# painel_meb.net
KiCad netlist of a schematic drawn in Altium Designer
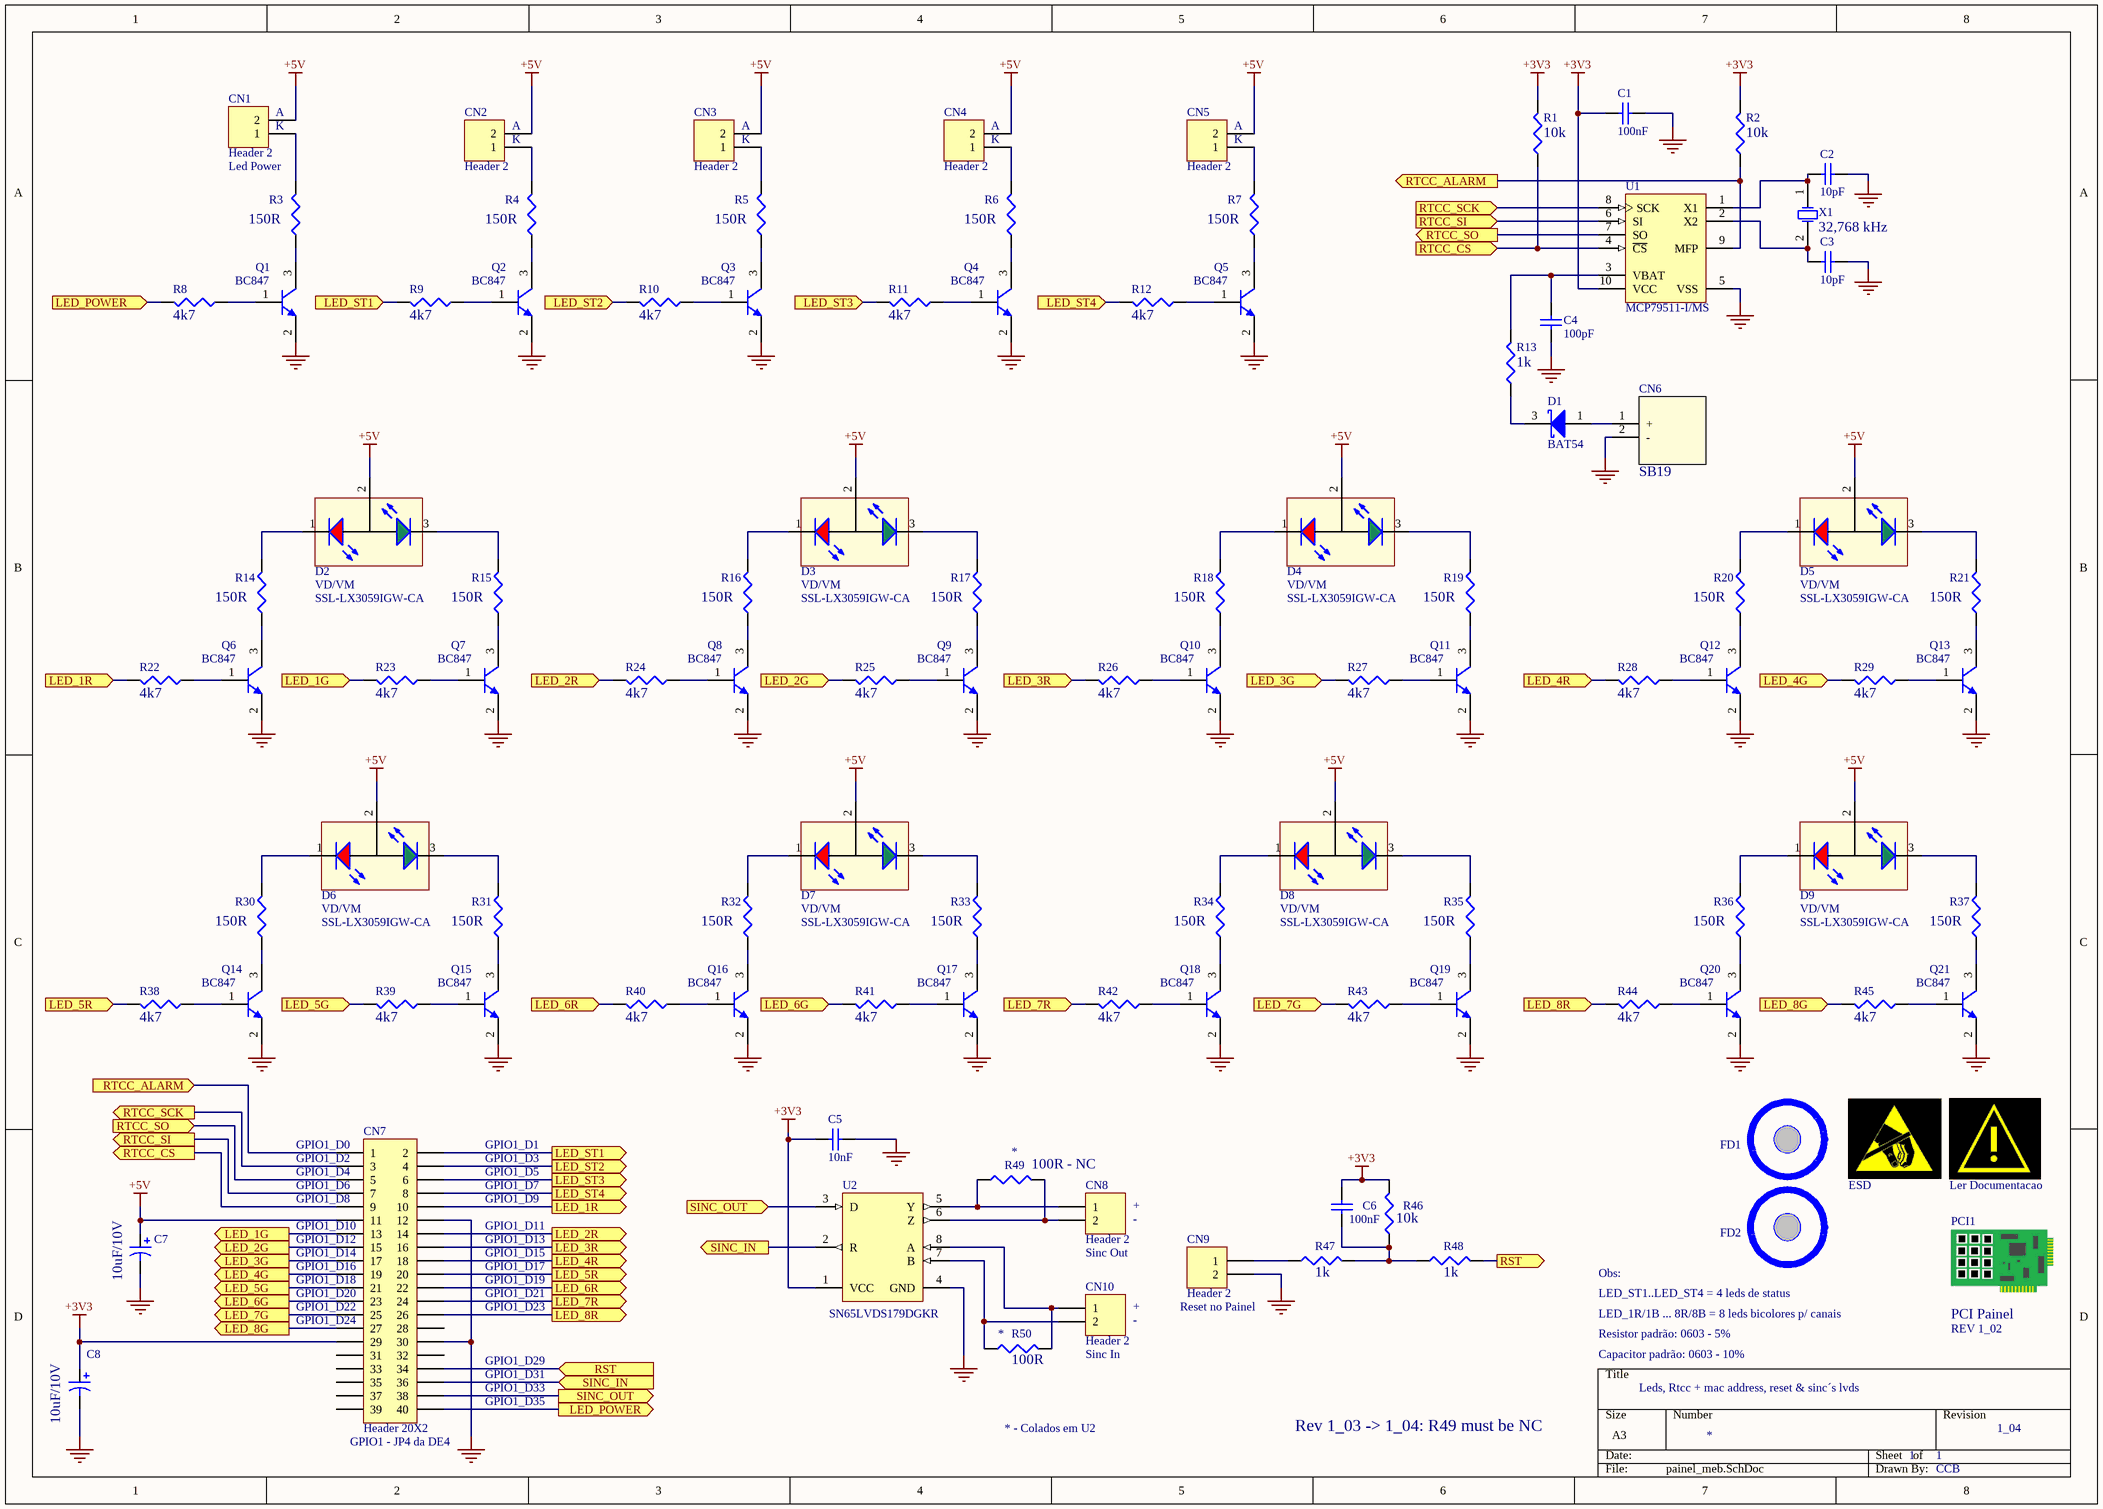
[diagram p0: painel_meb.SchDoc]

(export (version "E")
  (design (tool "Eeschema 10.0.6"))
  (components
    (comp (ref "AT1")
      (value "##nl")
      (footprint "LEIA_DOCUMENTACAO")
      (description "ATENCAO")
      (fields (field (name "VALOR") "Ler Documentacao"))
      (libsource (lib "SIMBOLOS") (part "ATENCAO"))
    )
    (comp (ref "C1")
      (value "Capacitor Cerâmico SMD")
      (footprint "0603 - CAP - montagem na maquina")
      (fields (field (name "VALOR") "100nF"))
      (libsource (lib "Miscellaneous Devices") (part "Capacitor Cerâmico SMD"))
    )
    (comp (ref "C2")
      (value "Capacitor Cerâmico SMD")
      (footprint "0603 - CAP - montagem na maquina")
      (fields (field (name "VALOR") "10pF"))
      (libsource (lib "Miscellaneous Devices") (part "Capacitor Cerâmico SMD"))
    )
    (comp (ref "C3")
      (value "Capacitor Cerâmico SMD")
      (footprint "0603 - CAP - montagem na maquina")
      (fields (field (name "VALOR") "10pF"))
      (libsource (lib "Miscellaneous Devices") (part "Capacitor Cerâmico SMD"))
    )
    (comp (ref "C4")
      (value "Capacitor Cerâmico SMD")
      (footprint "0603 - CAP - montagem na maquina")
      (fields (field (name "VALOR") "100pF"))
      (libsource (lib "Miscellaneous Devices") (part "Capacitor Cerâmico SMD"))
    )
    (comp (ref "C5")
      (value "Capacitor Cerâmico SMD")
      (footprint "0603 - CAP - montagem na maquina")
      (fields (field (name "VALOR") "10nF"))
      (libsource (lib "Miscellaneous Devices") (part "Capacitor Cerâmico SMD"))
    )
    (comp (ref "C6")
      (value "Capacitor Cerâmico SMD")
      (footprint "0603 - CAP - montagem na maquina")
      (fields (field (name "VALOR") "100nF"))
      (libsource (lib "Miscellaneous Devices") (part "Capacitor Cerâmico SMD"))
    )
    (comp (ref "C7")
      (value "Capacitor de tântalo")
      (footprint "CASE-B")
      (fields (field (name "VALOR") "10uF/10V"))
      (libsource (lib "Miscellaneous Devices") (part "Capacitor de tântalo"))
    )
    (comp (ref "C8")
      (value "Capacitor de tântalo")
      (footprint "CASE-B")
      (fields (field (name "VALOR") "10uF/10V"))
      (libsource (lib "Miscellaneous Devices") (part "Capacitor de tântalo"))
    )
    (comp (ref "CN1")
      (value "Header 2")
      (footprint "HDR1X2")
      (description "Header, 2-Pin")
      (fields (field (name "PUBLISHER") "Altium Limited"))
      (libsource (lib "Miscellaneous Connectors") (part "Header 2"))
    )
    (comp (ref "CN2")
      (value "Header 2")
      (footprint "HDR1X2")
      (description "Header, 2-Pin")
      (fields (field (name "PUBLISHER") "Altium Limited"))
      (libsource (lib "Miscellaneous Connectors") (part "Header 2"))
    )
    (comp (ref "CN3")
      (value "Header 2")
      (footprint "HDR1X2")
      (description "Header, 2-Pin")
      (fields (field (name "PUBLISHER") "Altium Limited"))
      (libsource (lib "Miscellaneous Connectors") (part "Header 2"))
    )
    (comp (ref "CN4")
      (value "Header 2")
      (footprint "HDR1X2")
      (description "Header, 2-Pin")
      (fields (field (name "PUBLISHER") "Altium Limited"))
      (libsource (lib "Miscellaneous Connectors") (part "Header 2"))
    )
    (comp (ref "CN5")
      (value "Header 2")
      (footprint "HDR1X2")
      (description "Header, 2-Pin")
      (fields (field (name "PUBLISHER") "Altium Limited"))
      (libsource (lib "Miscellaneous Connectors") (part "Header 2"))
    )
    (comp (ref "CN6")
      (value "11.0137")
      (footprint "Soquete para bateria SB19")
      (description "Soquete para Bateria CR2032")
      (fields (field (name "PART NUMBER") "SB19"))
      (libsource (lib "METALTEX") (part "Soquete para Bateria CR2032"))
    )
    (comp (ref "CN7")
      (value "Header 20X2")
      (footprint "HDR2X20")
      (description "Header, 20-Pin, Dual row")
      (fields (field (name "PUBLISHER") "Altium Limited"))
      (libsource (lib "Miscellaneous Connectors") (part "Header 20X2"))
    )
    (comp (ref "CN8")
      (value "Header 2")
      (footprint "HDR1X2")
      (description "Header, 2-Pin")
      (fields (field (name "PUBLISHER") "Altium Limited"))
      (libsource (lib "") (part "Header 2_1"))
    )
    (comp (ref "CN9")
      (value "Header 2")
      (footprint "HDR1X2")
      (description "Header, 2-Pin")
      (fields (field (name "PUBLISHER") "Altium Limited"))
      (libsource (lib "") (part "Header 2_2"))
    )
    (comp (ref "CN10")
      (value "Header 2")
      (footprint "HDR1X2")
      (description "Header, 2-Pin")
      (fields (field (name "PUBLISHER") "Altium Limited"))
      (libsource (lib "") (part "Header 2_1"))
    )
    (comp (ref "D1")
      (value "04.0100")
      (footprint "SOT23-3N - BAT54FAIRCHILD")
      (description "Diodo Schottky")
      (fields (field (name "PART NUMBER") "BAT54"))
      (libsource (lib "FSC Discrete Diode") (part "BAT54"))
    )
    (comp (ref "D2")
      (value "SSL-LX3059IGW-CA")
      (footprint "Led 3mm bicolor")
      (description "Led bicolor pth 3mm verde/vermelho")
      (fields (field (name "VALOR") "VD/VM") (field (name "PART NUMBER") "SSL-LX3059IGW-CA"))
      (libsource (lib "lumex") (part "SSL-LX3059IGW-CA"))
    )
    (comp (ref "D3")
      (value "SSL-LX3059IGW-CA")
      (footprint "Led 3mm bicolor")
      (description "Led bicolor pth 3mm verde/vermelho")
      (fields (field (name "VALOR") "VD/VM") (field (name "PART NUMBER") "SSL-LX3059IGW-CA"))
      (libsource (lib "lumex") (part "SSL-LX3059IGW-CA"))
    )
    (comp (ref "D4")
      (value "SSL-LX3059IGW-CA")
      (footprint "Led 3mm bicolor")
      (description "Led bicolor pth 3mm verde/vermelho")
      (fields (field (name "VALOR") "VD/VM") (field (name "PART NUMBER") "SSL-LX3059IGW-CA"))
      (libsource (lib "lumex") (part "SSL-LX3059IGW-CA"))
    )
    (comp (ref "D5")
      (value "SSL-LX3059IGW-CA")
      (footprint "Led 3mm bicolor")
      (description "Led bicolor pth 3mm verde/vermelho")
      (fields (field (name "VALOR") "VD/VM") (field (name "PART NUMBER") "SSL-LX3059IGW-CA"))
      (libsource (lib "lumex") (part "SSL-LX3059IGW-CA"))
    )
    (comp (ref "D6")
      (value "SSL-LX3059IGW-CA")
      (footprint "Led 3mm bicolor")
      (description "Led bicolor pth 3mm verde/vermelho")
      (fields (field (name "VALOR") "VD/VM") (field (name "PART NUMBER") "SSL-LX3059IGW-CA"))
      (libsource (lib "lumex") (part "SSL-LX3059IGW-CA"))
    )
    (comp (ref "D7")
      (value "SSL-LX3059IGW-CA")
      (footprint "Led 3mm bicolor")
      (description "Led bicolor pth 3mm verde/vermelho")
      (fields (field (name "VALOR") "VD/VM") (field (name "PART NUMBER") "SSL-LX3059IGW-CA"))
      (libsource (lib "lumex") (part "SSL-LX3059IGW-CA"))
    )
    (comp (ref "D8")
      (value "SSL-LX3059IGW-CA")
      (footprint "Led 3mm bicolor")
      (description "Led bicolor pth 3mm verde/vermelho")
      (fields (field (name "VALOR") "VD/VM") (field (name "PART NUMBER") "SSL-LX3059IGW-CA"))
      (libsource (lib "lumex") (part "SSL-LX3059IGW-CA"))
    )
    (comp (ref "D9")
      (value "SSL-LX3059IGW-CA")
      (footprint "Led 3mm bicolor")
      (description "Led bicolor pth 3mm verde/vermelho")
      (fields (field (name "VALOR") "VD/VM") (field (name "PART NUMBER") "SSL-LX3059IGW-CA"))
      (libsource (lib "lumex") (part "SSL-LX3059IGW-CA"))
    )
    (comp (ref "ESD1")
      (value "##nl")
      (footprint "ESTATICA")
      (description "ESD")
      (fields (field (name "VALOR") "ESD"))
      (libsource (lib "SIMBOLOS") (part "ESD"))
    )
    (comp (ref "FD1")
      (value "##nl")
      (footprint "FIDUCIAL")
      (description "Fiducial")
      (libsource (lib "PERIFERICOS") (part "Fiducial"))
    )
    (comp (ref "FD2")
      (value "##nl")
      (footprint "FIDUCIAL")
      (description "Fiducial")
      (libsource (lib "PERIFERICOS") (part "Fiducial"))
    )
    (comp (ref "PCI1")
      (value "30.????")
      (description "PCI")
      (fields (field (name "VALOR") "PCI Painel") (field (name "REV") "REV 1_02"))
      (libsource (lib "PCI") (part "PCI"))
    )
    (comp (ref "Q1")
      (value "QNPN")
      (footprint "SOT-23B")
      (description "NPN Bipolar Transistor")
      (fields (field (name "ALTIUM_UNNAMED_1") "BC847") (field (name "PUBLISHER") "Altium Limited"))
      (libsource (lib "Miscellaneous Devices") (part "QNPN"))
    )
    (comp (ref "Q2")
      (value "QNPN")
      (footprint "SOT-23B")
      (description "NPN Bipolar Transistor")
      (fields (field (name "VALOR") "BC847") (field (name "PUBLISHER") "Altium Limited"))
      (libsource (lib "Miscellaneous Devices") (part "QNPN"))
    )
    (comp (ref "Q3")
      (value "QNPN")
      (footprint "SOT-23B")
      (description "NPN Bipolar Transistor")
      (fields (field (name "ALTIUM_UNNAMED_1") "BC847") (field (name "PUBLISHER") "Altium Limited"))
      (libsource (lib "Miscellaneous Devices") (part "QNPN"))
    )
    (comp (ref "Q4")
      (value "QNPN")
      (footprint "SOT-23B")
      (description "NPN Bipolar Transistor")
      (fields (field (name "ALTIUM_UNNAMED_1") "BC847") (field (name "PUBLISHER") "Altium Limited"))
      (libsource (lib "Miscellaneous Devices") (part "QNPN"))
    )
    (comp (ref "Q5")
      (value "QNPN")
      (footprint "SOT-23B")
      (description "NPN Bipolar Transistor")
      (fields (field (name "ALTIUM_UNNAMED_1") "BC847") (field (name "PUBLISHER") "Altium Limited"))
      (libsource (lib "Miscellaneous Devices") (part "QNPN"))
    )
    (comp (ref "Q6")
      (value "QNPN")
      (footprint "SOT-23B")
      (description "NPN Bipolar Transistor")
      (fields (field (name "ALTIUM_UNNAMED_1") "BC847") (field (name "PUBLISHER") "Altium Limited"))
      (libsource (lib "Miscellaneous Devices") (part "QNPN"))
    )
    (comp (ref "Q7")
      (value "QNPN")
      (footprint "SOT-23B")
      (description "NPN Bipolar Transistor")
      (fields (field (name "ALTIUM_UNNAMED_1") "BC847") (field (name "PUBLISHER") "Altium Limited"))
      (libsource (lib "Miscellaneous Devices") (part "QNPN"))
    )
    (comp (ref "Q8")
      (value "QNPN")
      (footprint "SOT-23B")
      (description "NPN Bipolar Transistor")
      (fields (field (name "ALTIUM_UNNAMED_1") "BC847") (field (name "PUBLISHER") "Altium Limited"))
      (libsource (lib "Miscellaneous Devices") (part "QNPN"))
    )
    (comp (ref "Q9")
      (value "QNPN")
      (footprint "SOT-23B")
      (description "NPN Bipolar Transistor")
      (fields (field (name "ALTIUM_UNNAMED_1") "BC847") (field (name "PUBLISHER") "Altium Limited"))
      (libsource (lib "Miscellaneous Devices") (part "QNPN"))
    )
    (comp (ref "Q10")
      (value "QNPN")
      (footprint "SOT-23B")
      (description "NPN Bipolar Transistor")
      (fields (field (name "ALTIUM_UNNAMED_1") "BC847") (field (name "PUBLISHER") "Altium Limited"))
      (libsource (lib "Miscellaneous Devices") (part "QNPN"))
    )
    (comp (ref "Q11")
      (value "QNPN")
      (footprint "SOT-23B")
      (description "NPN Bipolar Transistor")
      (fields (field (name "ALTIUM_UNNAMED_1") "BC847") (field (name "PUBLISHER") "Altium Limited"))
      (libsource (lib "Miscellaneous Devices") (part "QNPN"))
    )
    (comp (ref "Q12")
      (value "QNPN")
      (footprint "SOT-23B")
      (description "NPN Bipolar Transistor")
      (fields (field (name "ALTIUM_UNNAMED_1") "BC847") (field (name "PUBLISHER") "Altium Limited"))
      (libsource (lib "Miscellaneous Devices") (part "QNPN"))
    )
    (comp (ref "Q13")
      (value "QNPN")
      (footprint "SOT-23B")
      (description "NPN Bipolar Transistor")
      (fields (field (name "ALTIUM_UNNAMED_1") "BC847") (field (name "PUBLISHER") "Altium Limited"))
      (libsource (lib "Miscellaneous Devices") (part "QNPN"))
    )
    (comp (ref "Q14")
      (value "QNPN")
      (footprint "SOT-23B")
      (description "NPN Bipolar Transistor")
      (fields (field (name "ALTIUM_UNNAMED_1") "BC847") (field (name "PUBLISHER") "Altium Limited"))
      (libsource (lib "Miscellaneous Devices") (part "QNPN"))
    )
    (comp (ref "Q15")
      (value "QNPN")
      (footprint "SOT-23B")
      (description "NPN Bipolar Transistor")
      (fields (field (name "ALTIUM_UNNAMED_1") "BC847") (field (name "PUBLISHER") "Altium Limited"))
      (libsource (lib "Miscellaneous Devices") (part "QNPN"))
    )
    (comp (ref "Q16")
      (value "QNPN")
      (footprint "SOT-23B")
      (description "NPN Bipolar Transistor")
      (fields (field (name "ALTIUM_UNNAMED_1") "BC847") (field (name "PUBLISHER") "Altium Limited"))
      (libsource (lib "Miscellaneous Devices") (part "QNPN"))
    )
    (comp (ref "Q17")
      (value "QNPN")
      (footprint "SOT-23B")
      (description "NPN Bipolar Transistor")
      (fields (field (name "ALTIUM_UNNAMED_1") "BC847") (field (name "PUBLISHER") "Altium Limited"))
      (libsource (lib "Miscellaneous Devices") (part "QNPN"))
    )
    (comp (ref "Q18")
      (value "QNPN")
      (footprint "SOT-23B")
      (description "NPN Bipolar Transistor")
      (fields (field (name "ALTIUM_UNNAMED_1") "BC847") (field (name "PUBLISHER") "Altium Limited"))
      (libsource (lib "Miscellaneous Devices") (part "QNPN"))
    )
    (comp (ref "Q19")
      (value "QNPN")
      (footprint "SOT-23B")
      (description "NPN Bipolar Transistor")
      (fields (field (name "ALTIUM_UNNAMED_1") "BC847") (field (name "PUBLISHER") "Altium Limited"))
      (libsource (lib "Miscellaneous Devices") (part "QNPN"))
    )
    (comp (ref "Q20")
      (value "QNPN")
      (footprint "SOT-23B")
      (description "NPN Bipolar Transistor")
      (fields (field (name "ALTIUM_UNNAMED_1") "BC847") (field (name "PUBLISHER") "Altium Limited"))
      (libsource (lib "Miscellaneous Devices") (part "QNPN"))
    )
    (comp (ref "Q21")
      (value "QNPN")
      (footprint "SOT-23B")
      (description "NPN Bipolar Transistor")
      (fields (field (name "ALTIUM_UNNAMED_1") "BC847") (field (name "PUBLISHER") "Altium Limited"))
      (libsource (lib "Miscellaneous Devices") (part "QNPN"))
    )
    (comp (ref "R1")
      (value "Res3")
      (footprint "0603 - MONTAGEM MÁQUINA")
      (description "Resistor")
      (fields (field (name "VALOR") "10k"))
      (libsource (lib "Miscellaneous Devices") (part "Res3"))
    )
    (comp (ref "R2")
      (value "Res3")
      (footprint "0603 - MONTAGEM MÁQUINA")
      (description "Resistor")
      (fields (field (name "VALOR") "10k"))
      (libsource (lib "Miscellaneous Devices") (part "Res3"))
    )
    (comp (ref "R3")
      (value "Res3")
      (footprint "0603 - MONTAGEM MÁQUINA")
      (description "Resistor")
      (fields (field (name "VALOR") "150R"))
      (libsource (lib "Miscellaneous Devices") (part "Res3"))
    )
    (comp (ref "R4")
      (value "Res3")
      (footprint "0603 - MONTAGEM MÁQUINA")
      (description "Resistor")
      (fields (field (name "VALOR") "150R"))
      (libsource (lib "Miscellaneous Devices") (part "Res3"))
    )
    (comp (ref "R5")
      (value "Res3")
      (footprint "0603 - MONTAGEM MÁQUINA")
      (description "Resistor")
      (fields (field (name "VALOR") "150R"))
      (libsource (lib "Miscellaneous Devices") (part "Res3"))
    )
    (comp (ref "R6")
      (value "Res3")
      (footprint "0603 - MONTAGEM MÁQUINA")
      (description "Resistor")
      (fields (field (name "VALOR") "150R"))
      (libsource (lib "Miscellaneous Devices") (part "Res3"))
    )
    (comp (ref "R7")
      (value "Res3")
      (footprint "0603 - MONTAGEM MÁQUINA")
      (description "Resistor")
      (fields (field (name "VALOR") "150R"))
      (libsource (lib "Miscellaneous Devices") (part "Res3"))
    )
    (comp (ref "R8")
      (value "Res3")
      (footprint "0603 - MONTAGEM MÁQUINA")
      (description "Resistor")
      (fields (field (name "VALOR") "4k7"))
      (libsource (lib "Miscellaneous Devices") (part "Res3"))
    )
    (comp (ref "R9")
      (value "Res3")
      (footprint "0603 - MONTAGEM MÁQUINA")
      (description "Resistor")
      (fields (field (name "VALOR") "4k7"))
      (libsource (lib "Miscellaneous Devices") (part "Res3"))
    )
    (comp (ref "R10")
      (value "Res3")
      (footprint "0603 - MONTAGEM MÁQUINA")
      (description "Resistor")
      (fields (field (name "VALOR") "4k7"))
      (libsource (lib "Miscellaneous Devices") (part "Res3"))
    )
    (comp (ref "R11")
      (value "Res3")
      (footprint "0603 - MONTAGEM MÁQUINA")
      (description "Resistor")
      (fields (field (name "VALOR") "4k7"))
      (libsource (lib "Miscellaneous Devices") (part "Res3"))
    )
    (comp (ref "R12")
      (value "Res3")
      (footprint "0603 - MONTAGEM MÁQUINA")
      (description "Resistor")
      (fields (field (name "VALOR") "4k7"))
      (libsource (lib "Miscellaneous Devices") (part "Res3"))
    )
    (comp (ref "R13")
      (value "Res3")
      (footprint "0603 - MONTAGEM MÁQUINA")
      (description "Resistor")
      (fields (field (name "VALOR") "1k"))
      (libsource (lib "Miscellaneous Devices") (part "Res3"))
    )
    (comp (ref "R14")
      (value "Res3")
      (footprint "0603 - MONTAGEM MÁQUINA")
      (description "Resistor")
      (fields (field (name "VALOR") "150R"))
      (libsource (lib "Miscellaneous Devices") (part "Res3"))
    )
    (comp (ref "R15")
      (value "Res3")
      (footprint "0603 - MONTAGEM MÁQUINA")
      (description "Resistor")
      (fields (field (name "VALOR") "150R"))
      (libsource (lib "Miscellaneous Devices") (part "Res3"))
    )
    (comp (ref "R16")
      (value "Res3")
      (footprint "0603 - MONTAGEM MÁQUINA")
      (description "Resistor")
      (fields (field (name "VALOR") "150R"))
      (libsource (lib "Miscellaneous Devices") (part "Res3"))
    )
    (comp (ref "R17")
      (value "Res3")
      (footprint "0603 - MONTAGEM MÁQUINA")
      (description "Resistor")
      (fields (field (name "VALOR") "150R"))
      (libsource (lib "Miscellaneous Devices") (part "Res3"))
    )
    (comp (ref "R18")
      (value "Res3")
      (footprint "0603 - MONTAGEM MÁQUINA")
      (description "Resistor")
      (fields (field (name "VALOR") "150R"))
      (libsource (lib "Miscellaneous Devices") (part "Res3"))
    )
    (comp (ref "R19")
      (value "Res3")
      (footprint "0603 - MONTAGEM MÁQUINA")
      (description "Resistor")
      (fields (field (name "VALOR") "150R"))
      (libsource (lib "Miscellaneous Devices") (part "Res3"))
    )
    (comp (ref "R20")
      (value "Res3")
      (footprint "0603 - MONTAGEM MÁQUINA")
      (description "Resistor")
      (fields (field (name "VALOR") "150R"))
      (libsource (lib "Miscellaneous Devices") (part "Res3"))
    )
    (comp (ref "R21")
      (value "Res3")
      (footprint "0603 - MONTAGEM MÁQUINA")
      (description "Resistor")
      (fields (field (name "VALOR") "150R"))
      (libsource (lib "Miscellaneous Devices") (part "Res3"))
    )
    (comp (ref "R22")
      (value "Res3")
      (footprint "0603 - MONTAGEM MÁQUINA")
      (description "Resistor")
      (fields (field (name "VALOR") "4k7"))
      (libsource (lib "Miscellaneous Devices") (part "Res3"))
    )
    (comp (ref "R23")
      (value "Res3")
      (footprint "0603 - MONTAGEM MÁQUINA")
      (description "Resistor")
      (fields (field (name "VALOR") "4k7"))
      (libsource (lib "Miscellaneous Devices") (part "Res3"))
    )
    (comp (ref "R24")
      (value "Res3")
      (footprint "0603 - MONTAGEM MÁQUINA")
      (description "Resistor")
      (fields (field (name "VALOR") "4k7"))
      (libsource (lib "Miscellaneous Devices") (part "Res3"))
    )
    (comp (ref "R25")
      (value "Res3")
      (footprint "0603 - MONTAGEM MÁQUINA")
      (description "Resistor")
      (fields (field (name "VALOR") "4k7"))
      (libsource (lib "Miscellaneous Devices") (part "Res3"))
    )
    (comp (ref "R26")
      (value "Res3")
      (footprint "0603 - MONTAGEM MÁQUINA")
      (description "Resistor")
      (fields (field (name "VALOR") "4k7"))
      (libsource (lib "Miscellaneous Devices") (part "Res3"))
    )
    (comp (ref "R27")
      (value "Res3")
      (footprint "0603 - MONTAGEM MÁQUINA")
      (description "Resistor")
      (fields (field (name "VALOR") "4k7"))
      (libsource (lib "Miscellaneous Devices") (part "Res3"))
    )
    (comp (ref "R28")
      (value "Res3")
      (footprint "0603 - MONTAGEM MÁQUINA")
      (description "Resistor")
      (fields (field (name "VALOR") "4k7"))
      (libsource (lib "Miscellaneous Devices") (part "Res3"))
    )
    (comp (ref "R29")
      (value "Res3")
      (footprint "0603 - MONTAGEM MÁQUINA")
      (description "Resistor")
      (fields (field (name "VALOR") "4k7"))
      (libsource (lib "Miscellaneous Devices") (part "Res3"))
    )
    (comp (ref "R30")
      (value "Res3")
      (footprint "0603 - MONTAGEM MÁQUINA")
      (description "Resistor")
      (fields (field (name "VALOR") "150R"))
      (libsource (lib "Miscellaneous Devices") (part "Res3"))
    )
    (comp (ref "R31")
      (value "Res3")
      (footprint "0603 - MONTAGEM MÁQUINA")
      (description "Resistor")
      (fields (field (name "VALOR") "150R"))
      (libsource (lib "Miscellaneous Devices") (part "Res3"))
    )
    (comp (ref "R32")
      (value "Res3")
      (footprint "0603 - MONTAGEM MÁQUINA")
      (description "Resistor")
      (fields (field (name "VALOR") "150R"))
      (libsource (lib "Miscellaneous Devices") (part "Res3"))
    )
    (comp (ref "R33")
      (value "Res3")
      (footprint "0603 - MONTAGEM MÁQUINA")
      (description "Resistor")
      (fields (field (name "VALOR") "150R"))
      (libsource (lib "Miscellaneous Devices") (part "Res3"))
    )
    (comp (ref "R34")
      (value "Res3")
      (footprint "0603 - MONTAGEM MÁQUINA")
      (description "Resistor")
      (fields (field (name "VALOR") "150R"))
      (libsource (lib "Miscellaneous Devices") (part "Res3"))
    )
    (comp (ref "R35")
      (value "Res3")
      (footprint "0603 - MONTAGEM MÁQUINA")
      (description "Resistor")
      (fields (field (name "VALOR") "150R"))
      (libsource (lib "Miscellaneous Devices") (part "Res3"))
    )
    (comp (ref "R36")
      (value "Res3")
      (footprint "0603 - MONTAGEM MÁQUINA")
      (description "Resistor")
      (fields (field (name "VALOR") "150R"))
      (libsource (lib "Miscellaneous Devices") (part "Res3"))
    )
    (comp (ref "R37")
      (value "Res3")
      (footprint "0603 - MONTAGEM MÁQUINA")
      (description "Resistor")
      (fields (field (name "VALOR") "150R"))
      (libsource (lib "Miscellaneous Devices") (part "Res3"))
    )
    (comp (ref "R38")
      (value "Res3")
      (footprint "0603 - MONTAGEM MÁQUINA")
      (description "Resistor")
      (fields (field (name "VALOR") "4k7"))
      (libsource (lib "Miscellaneous Devices") (part "Res3"))
    )
    (comp (ref "R39")
      (value "Res3")
      (footprint "0603 - MONTAGEM MÁQUINA")
      (description "Resistor")
      (fields (field (name "VALOR") "4k7"))
      (libsource (lib "Miscellaneous Devices") (part "Res3"))
    )
    (comp (ref "R40")
      (value "Res3")
      (footprint "0603 - MONTAGEM MÁQUINA")
      (description "Resistor")
      (fields (field (name "VALOR") "4k7"))
      (libsource (lib "Miscellaneous Devices") (part "Res3"))
    )
    (comp (ref "R41")
      (value "Res3")
      (footprint "0603 - MONTAGEM MÁQUINA")
      (description "Resistor")
      (fields (field (name "VALOR") "4k7"))
      (libsource (lib "Miscellaneous Devices") (part "Res3"))
    )
    (comp (ref "R42")
      (value "Res3")
      (footprint "0603 - MONTAGEM MÁQUINA")
      (description "Resistor")
      (fields (field (name "VALOR") "4k7"))
      (libsource (lib "Miscellaneous Devices") (part "Res3"))
    )
    (comp (ref "R43")
      (value "Res3")
      (footprint "0603 - MONTAGEM MÁQUINA")
      (description "Resistor")
      (fields (field (name "VALOR") "4k7"))
      (libsource (lib "Miscellaneous Devices") (part "Res3"))
    )
    (comp (ref "R44")
      (value "Res3")
      (footprint "0603 - MONTAGEM MÁQUINA")
      (description "Resistor")
      (fields (field (name "VALOR") "4k7"))
      (libsource (lib "Miscellaneous Devices") (part "Res3"))
    )
    (comp (ref "R45")
      (value "Res3")
      (footprint "0603 - MONTAGEM MÁQUINA")
      (description "Resistor")
      (fields (field (name "VALOR") "4k7"))
      (libsource (lib "Miscellaneous Devices") (part "Res3"))
    )
    (comp (ref "R46")
      (value "Res3")
      (footprint "0603 - MONTAGEM MÁQUINA")
      (description "Resistor")
      (fields (field (name "VALOR") "10k"))
      (libsource (lib "Miscellaneous Devices") (part "Res3"))
    )
    (comp (ref "R47")
      (value "Res3")
      (footprint "0603 - MONTAGEM MÁQUINA")
      (description "Resistor")
      (fields (field (name "VALOR") "1k"))
      (libsource (lib "Miscellaneous Devices") (part "Res3"))
    )
    (comp (ref "R48")
      (value "Res3")
      (footprint "0603 - MONTAGEM MÁQUINA")
      (description "Resistor")
      (fields (field (name "VALOR") "1k"))
      (libsource (lib "Miscellaneous Devices") (part "Res3"))
    )
    (comp (ref "R49")
      (value "Res3")
      (footprint "0603 - MONTAGEM MÁQUINA")
      (description "Resistor")
      (fields (field (name "VALOR") "100R - NC"))
      (libsource (lib "Miscellaneous Devices") (part "Res3"))
    )
    (comp (ref "R50")
      (value "Res3")
      (footprint "0603 - MONTAGEM MÁQUINA")
      (description "Resistor")
      (fields (field (name "VALOR") "100R"))
      (libsource (lib "Miscellaneous Devices") (part "Res3"))
    )
    (comp (ref "U1")
      (value "MCP79511-I/MS")
      (footprint "MCHP-MSOP-MS10_N")
      (fields (field (name "MANUFACTURER") "Microchip"))
      (libsource (lib "Microchip Interface") (part "MCP79511-I/MS"))
    )
    (comp (ref "U2")
      (value "SN65LVDS179MDGKREP")
      (footprint "DGK8_L")
      (fields (field (name "MANUFACTURER") "Texas Instruments") (field (name "PARTNUMBER") "SN65LVDS179DGKR"))
      (libsource (lib "TI Interface LVDS M-LVDS ECL CML") (part "SN65LVDS179MDGKREP"))
    )
    (comp (ref "X1")
      (value "XTAL")
      (footprint "CRISTAL DT-38")
      (description "Cristal oscilador")
      (fields (field (name "VALOR") "32,768 kHz") (field (name "PUBLISHER") "Altium Limited"))
      (libsource (lib "Miscellaneous Devices") (part "XTAL"))
    )
  )
  (nets
    (net (code "1") (name "+3V3") (class "Default")
      (node (ref "C1") (pin "1") (pinfunction "1_1") (pintype "passive"))
      (node (ref "C5") (pin "1") (pinfunction "1_1") (pintype "passive"))
      (node (ref "C6") (pin "2") (pinfunction "2_2") (pintype "passive"))
      (node (ref "C8") (pin "1") (pinfunction "1_1") (pintype "passive"))
      (node (ref "CN7") (pin "29") (pinfunction "29_29") (pintype "passive"))
      (node (ref "R1") (pin "2") (pinfunction "2_2") (pintype "passive"))
      (node (ref "R2") (pin "2") (pinfunction "2_2") (pintype "passive"))
      (node (ref "R46") (pin "2") (pinfunction "2_2") (pintype "passive"))
      (node (ref "U1") (pin "10") (pinfunction "VCC_10") (pintype "power_in"))
      (node (ref "U2") (pin "1") (pinfunction "VCC_1") (pintype "power_in"))
    )
    (net (code "2") (name "+5V") (class "Default")
      (node (ref "C7") (pin "1") (pinfunction "1_1") (pintype "passive"))
      (node (ref "CN1") (pin "2") (pinfunction "2_2") (pintype "passive"))
      (node (ref "CN2") (pin "2") (pinfunction "2_2") (pintype "passive"))
      (node (ref "CN3") (pin "2") (pinfunction "2_2") (pintype "passive"))
      (node (ref "CN4") (pin "2") (pinfunction "2_2") (pintype "passive"))
      (node (ref "CN5") (pin "2") (pinfunction "2_2") (pintype "passive"))
      (node (ref "CN7") (pin "11") (pinfunction "11_11") (pintype "passive"))
      (node (ref "D2") (pin "2") (pinfunction "A_2") (pintype "passive"))
      (node (ref "D3") (pin "2") (pinfunction "A_2") (pintype "passive"))
      (node (ref "D4") (pin "2") (pinfunction "A_2") (pintype "passive"))
      (node (ref "D5") (pin "2") (pinfunction "A_2") (pintype "passive"))
      (node (ref "D6") (pin "2") (pinfunction "A_2") (pintype "passive"))
      (node (ref "D7") (pin "2") (pinfunction "A_2") (pintype "passive"))
      (node (ref "D8") (pin "2") (pinfunction "A_2") (pintype "passive"))
      (node (ref "D9") (pin "2") (pinfunction "A_2") (pintype "passive"))
    )
    (net (code "3") (name "/LED_1G") (class "Default")
      (node (ref "CN7") (pin "13") (pinfunction "13_13") (pintype "passive"))
      (node (ref "R23") (pin "2") (pinfunction "2_2") (pintype "passive"))
    )
    (net (code "4") (name "/LED_1R") (class "Default")
      (node (ref "CN7") (pin "10") (pinfunction "10_10") (pintype "passive"))
      (node (ref "R22") (pin "2") (pinfunction "2_2") (pintype "passive"))
    )
    (net (code "5") (name "/LED_2G") (class "Default")
      (node (ref "CN7") (pin "15") (pinfunction "15_15") (pintype "passive"))
      (node (ref "R25") (pin "2") (pinfunction "2_2") (pintype "passive"))
    )
    (net (code "6") (name "/LED_2R") (class "Default")
      (node (ref "CN7") (pin "14") (pinfunction "14_14") (pintype "passive"))
      (node (ref "R24") (pin "2") (pinfunction "2_2") (pintype "passive"))
    )
    (net (code "7") (name "/LED_3G") (class "Default")
      (node (ref "CN7") (pin "17") (pinfunction "17_17") (pintype "passive"))
      (node (ref "R27") (pin "2") (pinfunction "2_2") (pintype "passive"))
    )
    (net (code "8") (name "/LED_3R") (class "Default")
      (node (ref "CN7") (pin "16") (pinfunction "16_16") (pintype "passive"))
      (node (ref "R26") (pin "2") (pinfunction "2_2") (pintype "passive"))
    )
    (net (code "9") (name "/LED_4G") (class "Default")
      (node (ref "CN7") (pin "19") (pinfunction "19_19") (pintype "passive"))
      (node (ref "R29") (pin "2") (pinfunction "2_2") (pintype "passive"))
    )
    (net (code "10") (name "/LED_4R") (class "Default")
      (node (ref "CN7") (pin "18") (pinfunction "18_18") (pintype "passive"))
      (node (ref "R28") (pin "2") (pinfunction "2_2") (pintype "passive"))
    )
    (net (code "11") (name "/LED_5G") (class "Default")
      (node (ref "CN7") (pin "21") (pinfunction "21_21") (pintype "passive"))
      (node (ref "R39") (pin "2") (pinfunction "2_2") (pintype "passive"))
    )
    (net (code "12") (name "/LED_5R") (class "Default")
      (node (ref "CN7") (pin "20") (pinfunction "20_20") (pintype "passive"))
      (node (ref "R38") (pin "2") (pinfunction "2_2") (pintype "passive"))
    )
    (net (code "13") (name "/LED_6G") (class "Default")
      (node (ref "CN7") (pin "23") (pinfunction "23_23") (pintype "passive"))
      (node (ref "R41") (pin "2") (pinfunction "2_2") (pintype "passive"))
    )
    (net (code "14") (name "/LED_6R") (class "Default")
      (node (ref "CN7") (pin "22") (pinfunction "22_22") (pintype "passive"))
      (node (ref "R40") (pin "2") (pinfunction "2_2") (pintype "passive"))
    )
    (net (code "15") (name "/LED_7G") (class "Default")
      (node (ref "CN7") (pin "25") (pinfunction "25_25") (pintype "passive"))
      (node (ref "R43") (pin "2") (pinfunction "2_2") (pintype "passive"))
    )
    (net (code "16") (name "/LED_7R") (class "Default")
      (node (ref "CN7") (pin "24") (pinfunction "24_24") (pintype "passive"))
      (node (ref "R42") (pin "2") (pinfunction "2_2") (pintype "passive"))
    )
    (net (code "17") (name "/LED_8G") (class "Default")
      (node (ref "CN7") (pin "27") (pinfunction "27_27") (pintype "passive"))
      (node (ref "R45") (pin "2") (pinfunction "2_2") (pintype "passive"))
    )
    (net (code "18") (name "/LED_8R") (class "Default")
      (node (ref "CN7") (pin "26") (pinfunction "26_26") (pintype "passive"))
      (node (ref "R44") (pin "2") (pinfunction "2_2") (pintype "passive"))
    )
    (net (code "19") (name "/LED_POWER") (class "Default")
      (node (ref "CN7") (pin "40") (pinfunction "40_40") (pintype "passive"))
      (node (ref "R8") (pin "2") (pinfunction "2_2") (pintype "passive"))
    )
    (net (code "20") (name "/LED_ST1") (class "Default")
      (node (ref "CN7") (pin "2") (pinfunction "2_2") (pintype "passive"))
      (node (ref "R9") (pin "2") (pinfunction "2_2") (pintype "passive"))
    )
    (net (code "21") (name "/LED_ST2") (class "Default")
      (node (ref "CN7") (pin "4") (pinfunction "4_4") (pintype "passive"))
      (node (ref "R10") (pin "2") (pinfunction "2_2") (pintype "passive"))
    )
    (net (code "22") (name "/LED_ST3") (class "Default")
      (node (ref "CN7") (pin "6") (pinfunction "6_6") (pintype "passive"))
      (node (ref "R11") (pin "2") (pinfunction "2_2") (pintype "passive"))
    )
    (net (code "23") (name "/LED_ST4") (class "Default")
      (node (ref "CN7") (pin "8") (pinfunction "8_8") (pintype "passive"))
      (node (ref "R12") (pin "2") (pinfunction "2_2") (pintype "passive"))
    )
    (net (code "24") (name "/RST") (class "Default")
      (node (ref "CN7") (pin "34") (pinfunction "34_34") (pintype "passive"))
      (node (ref "R48") (pin "2") (pinfunction "2_2") (pintype "passive"))
    )
    (net (code "25") (name "/RTCC_ALARM") (class "Default")
      (node (ref "CN7") (pin "1") (pinfunction "1_1") (pintype "passive"))
      (node (ref "R2") (pin "1") (pinfunction "1_1") (pintype "passive"))
      (node (ref "U1") (pin "9") (pinfunction "MFP_9") (pintype "open_collector"))
    )
    (net (code "26") (name "/RTCC_CS") (class "Default")
      (node (ref "CN7") (pin "9") (pinfunction "9_9") (pintype "passive"))
      (node (ref "R1") (pin "1") (pinfunction "1_1") (pintype "passive"))
      (node (ref "U1") (pin "4") (pinfunction "~{CS}_4") (pintype "input"))
    )
    (net (code "27") (name "/RTCC_SCK") (class "Default")
      (node (ref "CN7") (pin "3") (pinfunction "3_3") (pintype "passive"))
      (node (ref "U1") (pin "8") (pinfunction "SCK_8") (pintype "input"))
    )
    (net (code "28") (name "/RTCC_SI") (class "Default")
      (node (ref "CN7") (pin "7") (pinfunction "7_7") (pintype "passive"))
      (node (ref "U1") (pin "6") (pinfunction "SI_6") (pintype "input"))
    )
    (net (code "29") (name "/RTCC_SO") (class "Default")
      (node (ref "CN7") (pin "5") (pinfunction "5_5") (pintype "passive"))
      (node (ref "U1") (pin "7") (pinfunction "SO_7") (pintype "tri_state"))
    )
    (net (code "30") (name "/SINC_IN") (class "Default")
      (node (ref "CN7") (pin "36") (pinfunction "36_36") (pintype "passive"))
      (node (ref "U2") (pin "2") (pinfunction "R_2") (pintype "output"))
    )
    (net (code "31") (name "/SINC_OUT") (class "Default")
      (node (ref "CN7") (pin "38") (pinfunction "38_38") (pintype "passive"))
      (node (ref "U2") (pin "3") (pinfunction "D_3") (pintype "input"))
    )
    (net (code "32") (name "GND") (class "Default")
      (node (ref "C1") (pin "2") (pinfunction "2_2") (pintype "passive"))
      (node (ref "C2") (pin "2") (pinfunction "2_2") (pintype "passive"))
      (node (ref "C3") (pin "2") (pinfunction "2_2") (pintype "passive"))
      (node (ref "C4") (pin "2") (pinfunction "2_2") (pintype "passive"))
      (node (ref "C5") (pin "2") (pinfunction "2_2") (pintype "passive"))
      (node (ref "C7") (pin "2") (pinfunction "2_2") (pintype "passive"))
      (node (ref "C8") (pin "2") (pinfunction "2_2") (pintype "passive"))
      (node (ref "CN6") (pin "2") (pinfunction "-_2") (pintype "passive"))
      (node (ref "CN7") (pin "12") (pinfunction "12_12") (pintype "passive"))
      (node (ref "CN7") (pin "30") (pinfunction "30_30") (pintype "passive"))
      (node (ref "CN9") (pin "2") (pinfunction "2_2") (pintype "passive"))
      (node (ref "Q1") (pin "2") (pinfunction "E_2") (pintype "passive"))
      (node (ref "Q10") (pin "2") (pinfunction "E_2") (pintype "passive"))
      (node (ref "Q11") (pin "2") (pinfunction "E_2") (pintype "passive"))
      (node (ref "Q12") (pin "2") (pinfunction "E_2") (pintype "passive"))
      (node (ref "Q13") (pin "2") (pinfunction "E_2") (pintype "passive"))
      (node (ref "Q14") (pin "2") (pinfunction "E_2") (pintype "passive"))
      (node (ref "Q15") (pin "2") (pinfunction "E_2") (pintype "passive"))
      (node (ref "Q16") (pin "2") (pinfunction "E_2") (pintype "passive"))
      (node (ref "Q17") (pin "2") (pinfunction "E_2") (pintype "passive"))
      (node (ref "Q18") (pin "2") (pinfunction "E_2") (pintype "passive"))
      (node (ref "Q19") (pin "2") (pinfunction "E_2") (pintype "passive"))
      (node (ref "Q2") (pin "2") (pinfunction "E_2") (pintype "passive"))
      (node (ref "Q20") (pin "2") (pinfunction "E_2") (pintype "passive"))
      (node (ref "Q21") (pin "2") (pinfunction "E_2") (pintype "passive"))
      (node (ref "Q3") (pin "2") (pinfunction "E_2") (pintype "passive"))
      (node (ref "Q4") (pin "2") (pinfunction "E_2") (pintype "passive"))
      (node (ref "Q5") (pin "2") (pinfunction "E_2") (pintype "passive"))
      (node (ref "Q6") (pin "2") (pinfunction "E_2") (pintype "passive"))
      (node (ref "Q7") (pin "2") (pinfunction "E_2") (pintype "passive"))
      (node (ref "Q8") (pin "2") (pinfunction "E_2") (pintype "passive"))
      (node (ref "Q9") (pin "2") (pinfunction "E_2") (pintype "passive"))
      (node (ref "U1") (pin "5") (pinfunction "VSS_5") (pintype "power_in"))
      (node (ref "U2") (pin "4") (pinfunction "GND_4") (pintype "power_in"))
    )
    (net (code "33") (name "Net-(C6-Pad1)") (class "Default")
      (node (ref "C6") (pin "1") (pinfunction "1_1") (pintype "passive"))
      (node (ref "R46") (pin "1") (pinfunction "1_1") (pintype "passive"))
      (node (ref "R47") (pin "2") (pinfunction "2_2") (pintype "passive"))
      (node (ref "R48") (pin "1") (pinfunction "1_1") (pintype "passive"))
    )
    (net (code "34") (name "Net-(CN1-Pad1)") (class "Default")
      (node (ref "CN1") (pin "1") (pinfunction "1_1") (pintype "passive"))
      (node (ref "R3") (pin "2") (pinfunction "2_2") (pintype "passive"))
    )
    (net (code "35") (name "Net-(CN2-Pad1)") (class "Default")
      (node (ref "CN2") (pin "1") (pinfunction "1_1") (pintype "passive"))
      (node (ref "R4") (pin "2") (pinfunction "2_2") (pintype "passive"))
    )
    (net (code "36") (name "Net-(CN3-Pad1)") (class "Default")
      (node (ref "CN3") (pin "1") (pinfunction "1_1") (pintype "passive"))
      (node (ref "R5") (pin "2") (pinfunction "2_2") (pintype "passive"))
    )
    (net (code "37") (name "Net-(CN4-Pad1)") (class "Default")
      (node (ref "CN4") (pin "1") (pinfunction "1_1") (pintype "passive"))
      (node (ref "R6") (pin "2") (pinfunction "2_2") (pintype "passive"))
    )
    (net (code "38") (name "Net-(CN5-Pad1)") (class "Default")
      (node (ref "CN5") (pin "1") (pinfunction "1_1") (pintype "passive"))
      (node (ref "R7") (pin "2") (pinfunction "2_2") (pintype "passive"))
    )
    (net (code "39") (name "Net-(CN6-+)") (class "Default")
      (node (ref "CN6") (pin "1") (pinfunction "+_1") (pintype "passive"))
      (node (ref "D1") (pin "1") (pinfunction "A_1") (pintype "passive"))
    )
    (net (code "40") (name "Net-(CN9-Pad1)") (class "Default")
      (node (ref "CN9") (pin "1") (pinfunction "1_1") (pintype "passive"))
      (node (ref "R47") (pin "1") (pinfunction "1_1") (pintype "passive"))
    )
    (net (code "41") (name "Net-(D1-K)") (class "Default")
      (node (ref "D1") (pin "3") (pinfunction "K_3") (pintype "passive"))
      (node (ref "R13") (pin "1") (pinfunction "1_1") (pintype "passive"))
    )
    (net (code "42") (name "Net-(D2-KG)") (class "Default")
      (node (ref "D2") (pin "3") (pinfunction "KG_3") (pintype "passive"))
      (node (ref "R15") (pin "2") (pinfunction "2_2") (pintype "passive"))
    )
    (net (code "43") (name "Net-(D2-KR)") (class "Default")
      (node (ref "D2") (pin "1") (pinfunction "KR_1") (pintype "passive"))
      (node (ref "R14") (pin "2") (pinfunction "2_2") (pintype "passive"))
    )
    (net (code "44") (name "Net-(D3-KG)") (class "Default")
      (node (ref "D3") (pin "3") (pinfunction "KG_3") (pintype "passive"))
      (node (ref "R17") (pin "2") (pinfunction "2_2") (pintype "passive"))
    )
    (net (code "45") (name "Net-(D3-KR)") (class "Default")
      (node (ref "D3") (pin "1") (pinfunction "KR_1") (pintype "passive"))
      (node (ref "R16") (pin "2") (pinfunction "2_2") (pintype "passive"))
    )
    (net (code "46") (name "Net-(D4-KG)") (class "Default")
      (node (ref "D4") (pin "3") (pinfunction "KG_3") (pintype "passive"))
      (node (ref "R19") (pin "2") (pinfunction "2_2") (pintype "passive"))
    )
    (net (code "47") (name "Net-(D4-KR)") (class "Default")
      (node (ref "D4") (pin "1") (pinfunction "KR_1") (pintype "passive"))
      (node (ref "R18") (pin "2") (pinfunction "2_2") (pintype "passive"))
    )
    (net (code "48") (name "Net-(D5-KG)") (class "Default")
      (node (ref "D5") (pin "3") (pinfunction "KG_3") (pintype "passive"))
      (node (ref "R21") (pin "2") (pinfunction "2_2") (pintype "passive"))
    )
    (net (code "49") (name "Net-(D5-KR)") (class "Default")
      (node (ref "D5") (pin "1") (pinfunction "KR_1") (pintype "passive"))
      (node (ref "R20") (pin "2") (pinfunction "2_2") (pintype "passive"))
    )
    (net (code "50") (name "Net-(D6-KG)") (class "Default")
      (node (ref "D6") (pin "3") (pinfunction "KG_3") (pintype "passive"))
      (node (ref "R31") (pin "2") (pinfunction "2_2") (pintype "passive"))
    )
    (net (code "51") (name "Net-(D6-KR)") (class "Default")
      (node (ref "D6") (pin "1") (pinfunction "KR_1") (pintype "passive"))
      (node (ref "R30") (pin "2") (pinfunction "2_2") (pintype "passive"))
    )
    (net (code "52") (name "Net-(D7-KG)") (class "Default")
      (node (ref "D7") (pin "3") (pinfunction "KG_3") (pintype "passive"))
      (node (ref "R33") (pin "2") (pinfunction "2_2") (pintype "passive"))
    )
    (net (code "53") (name "Net-(D7-KR)") (class "Default")
      (node (ref "D7") (pin "1") (pinfunction "KR_1") (pintype "passive"))
      (node (ref "R32") (pin "2") (pinfunction "2_2") (pintype "passive"))
    )
    (net (code "54") (name "Net-(D8-KG)") (class "Default")
      (node (ref "D8") (pin "3") (pinfunction "KG_3") (pintype "passive"))
      (node (ref "R35") (pin "2") (pinfunction "2_2") (pintype "passive"))
    )
    (net (code "55") (name "Net-(D8-KR)") (class "Default")
      (node (ref "D8") (pin "1") (pinfunction "KR_1") (pintype "passive"))
      (node (ref "R34") (pin "2") (pinfunction "2_2") (pintype "passive"))
    )
    (net (code "56") (name "Net-(D9-KG)") (class "Default")
      (node (ref "D9") (pin "3") (pinfunction "KG_3") (pintype "passive"))
      (node (ref "R37") (pin "2") (pinfunction "2_2") (pintype "passive"))
    )
    (net (code "57") (name "Net-(D9-KR)") (class "Default")
      (node (ref "D9") (pin "1") (pinfunction "KR_1") (pintype "passive"))
      (node (ref "R36") (pin "2") (pinfunction "2_2") (pintype "passive"))
    )
    (net (code "58") (name "Net-(Q1-B)") (class "Default")
      (node (ref "Q1") (pin "1") (pinfunction "B_1") (pintype "passive"))
      (node (ref "R8") (pin "1") (pinfunction "1_1") (pintype "passive"))
    )
    (net (code "59") (name "Net-(Q1-C)") (class "Default")
      (node (ref "Q1") (pin "3") (pinfunction "C_3") (pintype "passive"))
      (node (ref "R3") (pin "1") (pinfunction "1_1") (pintype "passive"))
    )
    (net (code "60") (name "Net-(Q2-B)") (class "Default")
      (node (ref "Q2") (pin "1") (pinfunction "B_1") (pintype "passive"))
      (node (ref "R9") (pin "1") (pinfunction "1_1") (pintype "passive"))
    )
    (net (code "61") (name "Net-(Q2-C)") (class "Default")
      (node (ref "Q2") (pin "3") (pinfunction "C_3") (pintype "passive"))
      (node (ref "R4") (pin "1") (pinfunction "1_1") (pintype "passive"))
    )
    (net (code "62") (name "Net-(Q3-B)") (class "Default")
      (node (ref "Q3") (pin "1") (pinfunction "B_1") (pintype "passive"))
      (node (ref "R10") (pin "1") (pinfunction "1_1") (pintype "passive"))
    )
    (net (code "63") (name "Net-(Q3-C)") (class "Default")
      (node (ref "Q3") (pin "3") (pinfunction "C_3") (pintype "passive"))
      (node (ref "R5") (pin "1") (pinfunction "1_1") (pintype "passive"))
    )
    (net (code "64") (name "Net-(Q4-B)") (class "Default")
      (node (ref "Q4") (pin "1") (pinfunction "B_1") (pintype "passive"))
      (node (ref "R11") (pin "1") (pinfunction "1_1") (pintype "passive"))
    )
    (net (code "65") (name "Net-(Q4-C)") (class "Default")
      (node (ref "Q4") (pin "3") (pinfunction "C_3") (pintype "passive"))
      (node (ref "R6") (pin "1") (pinfunction "1_1") (pintype "passive"))
    )
    (net (code "66") (name "Net-(Q5-B)") (class "Default")
      (node (ref "Q5") (pin "1") (pinfunction "B_1") (pintype "passive"))
      (node (ref "R12") (pin "1") (pinfunction "1_1") (pintype "passive"))
    )
    (net (code "67") (name "Net-(Q5-C)") (class "Default")
      (node (ref "Q5") (pin "3") (pinfunction "C_3") (pintype "passive"))
      (node (ref "R7") (pin "1") (pinfunction "1_1") (pintype "passive"))
    )
    (net (code "68") (name "Net-(Q6-B)") (class "Default")
      (node (ref "Q6") (pin "1") (pinfunction "B_1") (pintype "passive"))
      (node (ref "R22") (pin "1") (pinfunction "1_1") (pintype "passive"))
    )
    (net (code "69") (name "Net-(Q6-C)") (class "Default")
      (node (ref "Q6") (pin "3") (pinfunction "C_3") (pintype "passive"))
      (node (ref "R14") (pin "1") (pinfunction "1_1") (pintype "passive"))
    )
    (net (code "70") (name "Net-(Q7-B)") (class "Default")
      (node (ref "Q7") (pin "1") (pinfunction "B_1") (pintype "passive"))
      (node (ref "R23") (pin "1") (pinfunction "1_1") (pintype "passive"))
    )
    (net (code "71") (name "Net-(Q7-C)") (class "Default")
      (node (ref "Q7") (pin "3") (pinfunction "C_3") (pintype "passive"))
      (node (ref "R15") (pin "1") (pinfunction "1_1") (pintype "passive"))
    )
    (net (code "72") (name "Net-(Q8-B)") (class "Default")
      (node (ref "Q8") (pin "1") (pinfunction "B_1") (pintype "passive"))
      (node (ref "R24") (pin "1") (pinfunction "1_1") (pintype "passive"))
    )
    (net (code "73") (name "Net-(Q8-C)") (class "Default")
      (node (ref "Q8") (pin "3") (pinfunction "C_3") (pintype "passive"))
      (node (ref "R16") (pin "1") (pinfunction "1_1") (pintype "passive"))
    )
    (net (code "74") (name "Net-(Q9-B)") (class "Default")
      (node (ref "Q9") (pin "1") (pinfunction "B_1") (pintype "passive"))
      (node (ref "R25") (pin "1") (pinfunction "1_1") (pintype "passive"))
    )
    (net (code "75") (name "Net-(Q9-C)") (class "Default")
      (node (ref "Q9") (pin "3") (pinfunction "C_3") (pintype "passive"))
      (node (ref "R17") (pin "1") (pinfunction "1_1") (pintype "passive"))
    )
    (net (code "76") (name "Net-(Q10-B)") (class "Default")
      (node (ref "Q10") (pin "1") (pinfunction "B_1") (pintype "passive"))
      (node (ref "R26") (pin "1") (pinfunction "1_1") (pintype "passive"))
    )
    (net (code "77") (name "Net-(Q10-C)") (class "Default")
      (node (ref "Q10") (pin "3") (pinfunction "C_3") (pintype "passive"))
      (node (ref "R18") (pin "1") (pinfunction "1_1") (pintype "passive"))
    )
    (net (code "78") (name "Net-(Q11-B)") (class "Default")
      (node (ref "Q11") (pin "1") (pinfunction "B_1") (pintype "passive"))
      (node (ref "R27") (pin "1") (pinfunction "1_1") (pintype "passive"))
    )
    (net (code "79") (name "Net-(Q11-C)") (class "Default")
      (node (ref "Q11") (pin "3") (pinfunction "C_3") (pintype "passive"))
      (node (ref "R19") (pin "1") (pinfunction "1_1") (pintype "passive"))
    )
    (net (code "80") (name "Net-(Q12-B)") (class "Default")
      (node (ref "Q12") (pin "1") (pinfunction "B_1") (pintype "passive"))
      (node (ref "R28") (pin "1") (pinfunction "1_1") (pintype "passive"))
    )
    (net (code "81") (name "Net-(Q12-C)") (class "Default")
      (node (ref "Q12") (pin "3") (pinfunction "C_3") (pintype "passive"))
      (node (ref "R20") (pin "1") (pinfunction "1_1") (pintype "passive"))
    )
    (net (code "82") (name "Net-(Q13-B)") (class "Default")
      (node (ref "Q13") (pin "1") (pinfunction "B_1") (pintype "passive"))
      (node (ref "R29") (pin "1") (pinfunction "1_1") (pintype "passive"))
    )
    (net (code "83") (name "Net-(Q13-C)") (class "Default")
      (node (ref "Q13") (pin "3") (pinfunction "C_3") (pintype "passive"))
      (node (ref "R21") (pin "1") (pinfunction "1_1") (pintype "passive"))
    )
    (net (code "84") (name "Net-(Q14-B)") (class "Default")
      (node (ref "Q14") (pin "1") (pinfunction "B_1") (pintype "passive"))
      (node (ref "R38") (pin "1") (pinfunction "1_1") (pintype "passive"))
    )
    (net (code "85") (name "Net-(Q14-C)") (class "Default")
      (node (ref "Q14") (pin "3") (pinfunction "C_3") (pintype "passive"))
      (node (ref "R30") (pin "1") (pinfunction "1_1") (pintype "passive"))
    )
    (net (code "86") (name "Net-(Q15-B)") (class "Default")
      (node (ref "Q15") (pin "1") (pinfunction "B_1") (pintype "passive"))
      (node (ref "R39") (pin "1") (pinfunction "1_1") (pintype "passive"))
    )
    (net (code "87") (name "Net-(Q15-C)") (class "Default")
      (node (ref "Q15") (pin "3") (pinfunction "C_3") (pintype "passive"))
      (node (ref "R31") (pin "1") (pinfunction "1_1") (pintype "passive"))
    )
    (net (code "88") (name "Net-(Q16-B)") (class "Default")
      (node (ref "Q16") (pin "1") (pinfunction "B_1") (pintype "passive"))
      (node (ref "R40") (pin "1") (pinfunction "1_1") (pintype "passive"))
    )
    (net (code "89") (name "Net-(Q16-C)") (class "Default")
      (node (ref "Q16") (pin "3") (pinfunction "C_3") (pintype "passive"))
      (node (ref "R32") (pin "1") (pinfunction "1_1") (pintype "passive"))
    )
    (net (code "90") (name "Net-(Q17-B)") (class "Default")
      (node (ref "Q17") (pin "1") (pinfunction "B_1") (pintype "passive"))
      (node (ref "R41") (pin "1") (pinfunction "1_1") (pintype "passive"))
    )
    (net (code "91") (name "Net-(Q17-C)") (class "Default")
      (node (ref "Q17") (pin "3") (pinfunction "C_3") (pintype "passive"))
      (node (ref "R33") (pin "1") (pinfunction "1_1") (pintype "passive"))
    )
    (net (code "92") (name "Net-(Q18-B)") (class "Default")
      (node (ref "Q18") (pin "1") (pinfunction "B_1") (pintype "passive"))
      (node (ref "R42") (pin "1") (pinfunction "1_1") (pintype "passive"))
    )
    (net (code "93") (name "Net-(Q18-C)") (class "Default")
      (node (ref "Q18") (pin "3") (pinfunction "C_3") (pintype "passive"))
      (node (ref "R34") (pin "1") (pinfunction "1_1") (pintype "passive"))
    )
    (net (code "94") (name "Net-(Q19-B)") (class "Default")
      (node (ref "Q19") (pin "1") (pinfunction "B_1") (pintype "passive"))
      (node (ref "R43") (pin "1") (pinfunction "1_1") (pintype "passive"))
    )
    (net (code "95") (name "Net-(Q19-C)") (class "Default")
      (node (ref "Q19") (pin "3") (pinfunction "C_3") (pintype "passive"))
      (node (ref "R35") (pin "1") (pinfunction "1_1") (pintype "passive"))
    )
    (net (code "96") (name "Net-(Q20-B)") (class "Default")
      (node (ref "Q20") (pin "1") (pinfunction "B_1") (pintype "passive"))
      (node (ref "R44") (pin "1") (pinfunction "1_1") (pintype "passive"))
    )
    (net (code "97") (name "Net-(Q20-C)") (class "Default")
      (node (ref "Q20") (pin "3") (pinfunction "C_3") (pintype "passive"))
      (node (ref "R36") (pin "1") (pinfunction "1_1") (pintype "passive"))
    )
    (net (code "98") (name "Net-(Q21-B)") (class "Default")
      (node (ref "Q21") (pin "1") (pinfunction "B_1") (pintype "passive"))
      (node (ref "R45") (pin "1") (pinfunction "1_1") (pintype "passive"))
    )
    (net (code "99") (name "Net-(Q21-C)") (class "Default")
      (node (ref "Q21") (pin "3") (pinfunction "C_3") (pintype "passive"))
      (node (ref "R37") (pin "1") (pinfunction "1_1") (pintype "passive"))
    )
    (net (code "100") (name "Net-(U1-VBAT)") (class "Default")
      (node (ref "C4") (pin "1") (pinfunction "1_1") (pintype "passive"))
      (node (ref "R13") (pin "2") (pinfunction "2_2") (pintype "passive"))
      (node (ref "U1") (pin "3") (pinfunction "VBAT_3") (pintype "power_in"))
    )
    (net (code "101") (name "Net-(U1-X1)") (class "Default")
      (node (ref "C2") (pin "1") (pinfunction "1_1") (pintype "passive"))
      (node (ref "U1") (pin "1") (pinfunction "X1_1") (pintype "passive"))
      (node (ref "X1") (pin "1") (pinfunction "OSC1_1") (pintype "passive"))
    )
    (net (code "102") (name "Net-(U1-X2)") (class "Default")
      (node (ref "C3") (pin "1") (pinfunction "1_1") (pintype "passive"))
      (node (ref "U1") (pin "2") (pinfunction "X2_2") (pintype "passive"))
      (node (ref "X1") (pin "2") (pinfunction "OSC2_2") (pintype "passive"))
    )
    (net (code "103") (name "Net-(U2-A)") (class "Default")
      (node (ref "CN10") (pin "1") (pinfunction "1_1") (pintype "passive"))
      (node (ref "R50") (pin "2") (pinfunction "2_2") (pintype "passive"))
      (node (ref "U2") (pin "8") (pinfunction "A_8") (pintype "input"))
    )
    (net (code "104") (name "Net-(U2-B)") (class "Default")
      (node (ref "CN10") (pin "2") (pinfunction "2_2") (pintype "passive"))
      (node (ref "R50") (pin "1") (pinfunction "1_1") (pintype "passive"))
      (node (ref "U2") (pin "7") (pinfunction "B_7") (pintype "input"))
    )
    (net (code "105") (name "Net-(U2-Y)") (class "Default")
      (node (ref "CN8") (pin "1") (pinfunction "1_1") (pintype "passive"))
      (node (ref "R49") (pin "1") (pinfunction "1_1") (pintype "passive"))
      (node (ref "U2") (pin "5") (pinfunction "Y_5") (pintype "output"))
    )
    (net (code "106") (name "Net-(U2-Z)") (class "Default")
      (node (ref "CN8") (pin "2") (pinfunction "2_2") (pintype "passive"))
      (node (ref "R49") (pin "2") (pinfunction "2_2") (pintype "passive"))
      (node (ref "U2") (pin "6") (pinfunction "Z_6") (pintype "output"))
    )
    (net (code "107") (name "unconnected-(CN7-Pad28)") (class "Default")
      (node (ref "CN7") (pin "28") (pinfunction "28_28") (pintype "passive"))
    )
    (net (code "108") (name "unconnected-(CN7-Pad31)") (class "Default")
      (node (ref "CN7") (pin "31") (pinfunction "31_31") (pintype "passive"))
    )
    (net (code "109") (name "unconnected-(CN7-Pad32)") (class "Default")
      (node (ref "CN7") (pin "32") (pinfunction "32_32") (pintype "passive"))
    )
    (net (code "110") (name "unconnected-(CN7-Pad33)") (class "Default")
      (node (ref "CN7") (pin "33") (pinfunction "33_33") (pintype "passive"))
    )
    (net (code "111") (name "unconnected-(CN7-Pad35)") (class "Default")
      (node (ref "CN7") (pin "35") (pinfunction "35_35") (pintype "passive"))
    )
    (net (code "112") (name "unconnected-(CN7-Pad37)") (class "Default")
      (node (ref "CN7") (pin "37") (pinfunction "37_37") (pintype "passive"))
    )
    (net (code "113") (name "unconnected-(CN7-Pad39)") (class "Default")
      (node (ref "CN7") (pin "39") (pinfunction "39_39") (pintype "passive"))
    )
  )
)
